# LC_BigOne_-_TLC5940_driver.net
KiCad netlist of a schematic drawn in Altium Designer
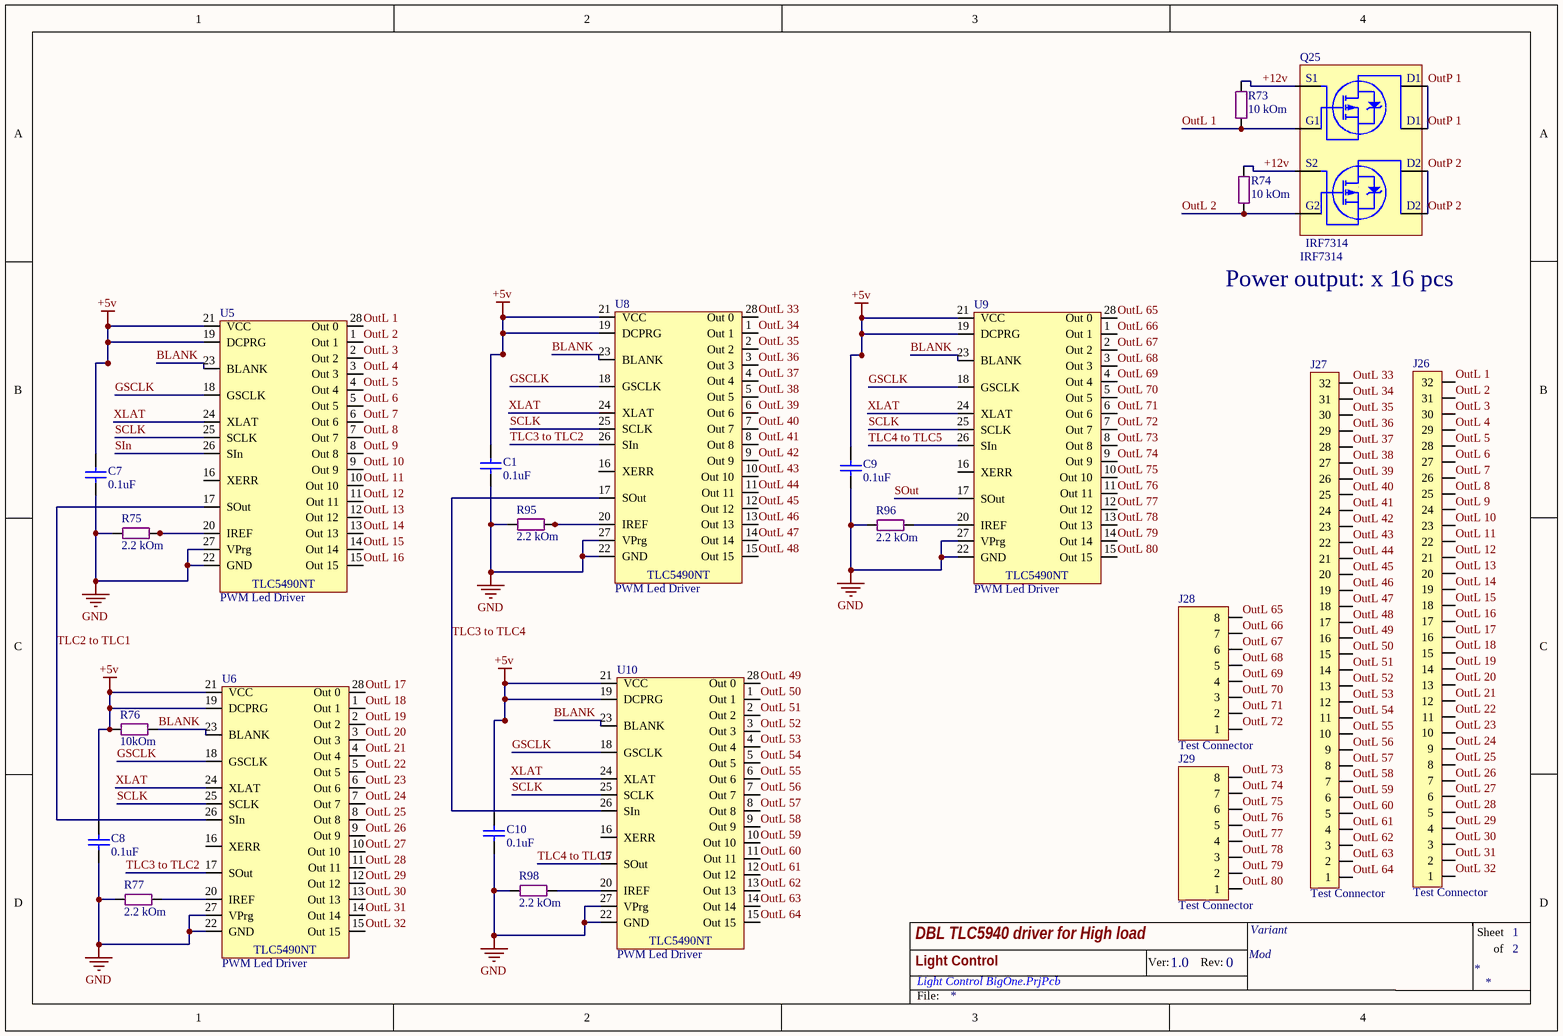
[diagram p0: LC BigOne - TLC5940 driver.SchDoc]

(export (version "E")
  (design (tool "Eeschema 10.0.6"))
  (components
    (comp (ref "C1")
      (value "0.1uF")
      (footprint "Capacitor:SMD 0805 (2012)")
      (description "Capacitor")
      (libsource (lib "Capacitor") (part "Cap SMD 0402-1812"))
    )
    (comp (ref "C7")
      (value "0.1uF")
      (footprint "Capacitor:SMD 0805 (2012)")
      (description "Capacitor")
      (libsource (lib "Capacitor") (part "Cap SMD 0402-1812"))
    )
    (comp (ref "C8")
      (value "0.1uF")
      (footprint "Capacitor:SMD 0805 (2012)")
      (description "Capacitor")
      (libsource (lib "Capacitor") (part "Cap SMD 0402-1812"))
    )
    (comp (ref "C9")
      (value "0.1uF")
      (footprint "Capacitor:SMD 0805 (2012)")
      (description "Capacitor")
      (libsource (lib "Capacitor") (part "Cap SMD 0402-1812"))
    )
    (comp (ref "C10")
      (value "0.1uF")
      (footprint "Capacitor:SMD 0805 (2012)")
      (description "Capacitor")
      (libsource (lib "Capacitor") (part "Cap SMD 0402-1812"))
    )
    (comp (ref "J26")
      (value "Test Connector")
      (footprint "Connector:LINE 2.54 x 32")
      (description "Vert, Sgl line, Male")
      (libsource (lib "Connector") (part "PLS-32"))
    )
    (comp (ref "J27")
      (value "Test Connector")
      (footprint "Connector:LINE 2.54 x 32")
      (description "Vert, Sgl line, Male")
      (libsource (lib "Connector") (part "PLS-32"))
    )
    (comp (ref "J28")
      (value "Test Connector")
      (footprint "Connector:Line 2.54 x 8")
      (description "Vert, Sgl line, Male")
      (libsource (lib "Connector") (part "PLS-8"))
    )
    (comp (ref "J29")
      (value "Test Connector")
      (footprint "Connector:Line 2.54 x 8")
      (description "Vert, Sgl line, Male")
      (libsource (lib "Connector") (part "PLS-8"))
    )
    (comp (ref "Q25")
      (value "IRF7314")
      (footprint "GeneralCases:SO8")
      (description "Dual P-Ch  20V - 0.058Ω - 5.3A")
      (libsource (lib "Transistor") (part "IRF7314"))
    )
    (comp (ref "R73")
      (value "10 kOm")
      (footprint "PassiveComponents:SMD 0805 (2012)")
      (libsource (lib "PassiveComponents") (part "Res All Types"))
    )
    (comp (ref "R74")
      (value "10 kOm")
      (footprint "PassiveComponents:SMD 0805 (2012)")
      (libsource (lib "PassiveComponents") (part "Res All Types"))
    )
    (comp (ref "R75")
      (value "2.2 kOm")
      (footprint "PassiveComponents:SMD 0805 (2012)")
      (libsource (lib "PassiveComponents") (part "Res All Types"))
    )
    (comp (ref "R76")
      (value "10kOm")
      (footprint "PassiveComponents:SMD 0805 (2012)")
      (libsource (lib "PassiveComponents") (part "Res All Types"))
    )
    (comp (ref "R77")
      (value "2.2 kOm")
      (footprint "PassiveComponents:SMD 0805 (2012)")
      (libsource (lib "PassiveComponents") (part "Res All Types"))
    )
    (comp (ref "R95")
      (value "2.2 kOm")
      (footprint "PassiveComponents:SMD 0805 (2012)")
      (libsource (lib "PassiveComponents") (part "Res All Types"))
    )
    (comp (ref "R96")
      (value "2.2 kOm")
      (footprint "PassiveComponents:SMD 0805 (2012)")
      (libsource (lib "PassiveComponents") (part "Res All Types"))
    )
    (comp (ref "R98")
      (value "2.2 kOm")
      (footprint "PassiveComponents:SMD 0805 (2012)")
      (libsource (lib "PassiveComponents") (part "Res All Types"))
    )
    (comp (ref "U5")
      (value "PWM Led Driver")
      (footprint "GeneralCases:DIP-28 (OVAL)")
      (description "16-Channel LED Driver With DOT Correction and Grayscale PWM Control")
      (libsource (lib "Chips") (part "TLC5940"))
    )
    (comp (ref "U6")
      (value "PWM Led Driver")
      (footprint "GeneralCases:DIP-28 (OVAL)")
      (description "16-Channel LED Driver With DOT Correction and Grayscale PWM Control")
      (libsource (lib "Chips") (part "TLC5940"))
    )
    (comp (ref "U8")
      (value "PWM Led Driver")
      (footprint "GeneralCases:DIP-28 (OVAL)")
      (description "16-Channel LED Driver With DOT Correction and Grayscale PWM Control")
      (libsource (lib "Chips") (part "TLC5940"))
    )
    (comp (ref "U9")
      (value "PWM Led Driver")
      (footprint "GeneralCases:DIP-28 (OVAL)")
      (description "16-Channel LED Driver With DOT Correction and Grayscale PWM Control")
      (libsource (lib "Chips") (part "TLC5940"))
    )
    (comp (ref "U10")
      (value "PWM Led Driver")
      (footprint "GeneralCases:DIP-28 (OVAL)")
      (description "16-Channel LED Driver With DOT Correction and Grayscale PWM Control")
      (libsource (lib "Chips") (part "TLC5940"))
    )
  )
  (nets
    (net (code "1") (name "+5v") (class "Default")
      (node (ref "C1") (pin "1") (pinfunction "1_1") (pintype "passive"))
      (node (ref "C10") (pin "1") (pinfunction "1_1") (pintype "passive"))
      (node (ref "C7") (pin "1") (pinfunction "1_1") (pintype "passive"))
      (node (ref "C8") (pin "1") (pinfunction "1_1") (pintype "passive"))
      (node (ref "C9") (pin "1") (pinfunction "1_1") (pintype "passive"))
      (node (ref "R76") (pin "1") (pinfunction "1_1") (pintype "passive"))
      (node (ref "U10") (pin "19") (pinfunction "DCPRG_19") (pintype "passive"))
      (node (ref "U10") (pin "21") (pinfunction "VCC_21") (pintype "passive"))
      (node (ref "U5") (pin "19") (pinfunction "DCPRG_19") (pintype "passive"))
      (node (ref "U5") (pin "21") (pinfunction "VCC_21") (pintype "passive"))
      (node (ref "U6") (pin "19") (pinfunction "DCPRG_19") (pintype "passive"))
      (node (ref "U6") (pin "21") (pinfunction "VCC_21") (pintype "passive"))
      (node (ref "U8") (pin "19") (pinfunction "DCPRG_19") (pintype "passive"))
      (node (ref "U8") (pin "21") (pinfunction "VCC_21") (pintype "passive"))
      (node (ref "U9") (pin "19") (pinfunction "DCPRG_19") (pintype "passive"))
      (node (ref "U9") (pin "21") (pinfunction "VCC_21") (pintype "passive"))
    )
    (net (code "2") (name "/+12v") (class "Default")
      (node (ref "Q25") (pin "1") (pinfunction "S_1") (pintype "passive"))
      (node (ref "Q25") (pin "3") (pinfunction "S_3") (pintype "passive"))
      (node (ref "R73") (pin "2") (pinfunction "2_2") (pintype "passive"))
      (node (ref "R74") (pin "2") (pinfunction "2_2") (pintype "passive"))
    )
    (net (code "3") (name "/BLANK") (class "Default")
      (node (ref "R76") (pin "2") (pinfunction "2_2") (pintype "passive"))
      (node (ref "U10") (pin "23") (pinfunction "BLANK_23") (pintype "passive"))
      (node (ref "U5") (pin "23") (pinfunction "BLANK_23") (pintype "passive"))
      (node (ref "U6") (pin "23") (pinfunction "BLANK_23") (pintype "passive"))
      (node (ref "U8") (pin "23") (pinfunction "BLANK_23") (pintype "passive"))
      (node (ref "U9") (pin "23") (pinfunction "BLANK_23") (pintype "passive"))
    )
    (net (code "4") (name "/GSCLK") (class "Default")
      (node (ref "U10") (pin "18") (pinfunction "GSCLK_18") (pintype "passive"))
      (node (ref "U5") (pin "18") (pinfunction "GSCLK_18") (pintype "passive"))
      (node (ref "U6") (pin "18") (pinfunction "GSCLK_18") (pintype "passive"))
      (node (ref "U8") (pin "18") (pinfunction "GSCLK_18") (pintype "passive"))
      (node (ref "U9") (pin "18") (pinfunction "GSCLK_18") (pintype "passive"))
    )
    (net (code "5") (name "/OutL 1") (class "Default")
      (node (ref "J26") (pin "32") (pinfunction "32_32") (pintype "passive"))
      (node (ref "Q25") (pin "2") (pinfunction "G_2") (pintype "passive"))
      (node (ref "R73") (pin "1") (pinfunction "1_1") (pintype "passive"))
      (node (ref "U5") (pin "28") (pinfunction "Out_0_28") (pintype "passive"))
    )
    (net (code "6") (name "/OutL 2") (class "Default")
      (node (ref "J26") (pin "31") (pinfunction "31_31") (pintype "passive"))
      (node (ref "Q25") (pin "4") (pinfunction "G_4") (pintype "passive"))
      (node (ref "R74") (pin "1") (pinfunction "1_1") (pintype "passive"))
      (node (ref "U5") (pin "1") (pinfunction "Out_1_1") (pintype "passive"))
    )
    (net (code "7") (name "/OutL 3") (class "Default")
      (node (ref "J26") (pin "30") (pinfunction "30_30") (pintype "passive"))
      (node (ref "U5") (pin "2") (pinfunction "Out_2_2") (pintype "passive"))
    )
    (net (code "8") (name "/OutL 4") (class "Default")
      (node (ref "J26") (pin "29") (pinfunction "29_29") (pintype "passive"))
      (node (ref "U5") (pin "3") (pinfunction "Out_3_3") (pintype "passive"))
    )
    (net (code "9") (name "/OutL 5") (class "Default")
      (node (ref "J26") (pin "28") (pinfunction "28_28") (pintype "passive"))
      (node (ref "U5") (pin "4") (pinfunction "Out_4_4") (pintype "passive"))
    )
    (net (code "10") (name "/OutL 6") (class "Default")
      (node (ref "J26") (pin "27") (pinfunction "27_27") (pintype "passive"))
      (node (ref "U5") (pin "5") (pinfunction "Out_5_5") (pintype "passive"))
    )
    (net (code "11") (name "/OutL 7") (class "Default")
      (node (ref "J26") (pin "26") (pinfunction "26_26") (pintype "passive"))
      (node (ref "U5") (pin "6") (pinfunction "Out_6_6") (pintype "passive"))
    )
    (net (code "12") (name "/OutL 8") (class "Default")
      (node (ref "J26") (pin "25") (pinfunction "25_25") (pintype "passive"))
      (node (ref "U5") (pin "7") (pinfunction "Out_7_7") (pintype "passive"))
    )
    (net (code "13") (name "/OutL 9") (class "Default")
      (node (ref "J26") (pin "24") (pinfunction "24_24") (pintype "passive"))
      (node (ref "U5") (pin "8") (pinfunction "Out_8_8") (pintype "passive"))
    )
    (net (code "14") (name "/OutL 10") (class "Default")
      (node (ref "J26") (pin "23") (pinfunction "23_23") (pintype "passive"))
      (node (ref "U5") (pin "9") (pinfunction "Out_9_9") (pintype "passive"))
    )
    (net (code "15") (name "/OutL 11") (class "Default")
      (node (ref "J26") (pin "22") (pinfunction "22_22") (pintype "passive"))
      (node (ref "U5") (pin "10") (pinfunction "Out_10_10") (pintype "passive"))
    )
    (net (code "16") (name "/OutL 12") (class "Default")
      (node (ref "J26") (pin "21") (pinfunction "21_21") (pintype "passive"))
      (node (ref "U5") (pin "11") (pinfunction "Out_11_11") (pintype "passive"))
    )
    (net (code "17") (name "/OutL 13") (class "Default")
      (node (ref "J26") (pin "20") (pinfunction "20_20") (pintype "passive"))
      (node (ref "U5") (pin "12") (pinfunction "Out_12_12") (pintype "passive"))
    )
    (net (code "18") (name "/OutL 14") (class "Default")
      (node (ref "J26") (pin "19") (pinfunction "19_19") (pintype "passive"))
      (node (ref "U5") (pin "13") (pinfunction "Out_13_13") (pintype "passive"))
    )
    (net (code "19") (name "/OutL 15") (class "Default")
      (node (ref "J26") (pin "18") (pinfunction "18_18") (pintype "passive"))
      (node (ref "U5") (pin "14") (pinfunction "Out_14_14") (pintype "passive"))
    )
    (net (code "20") (name "/OutL 16") (class "Default")
      (node (ref "J26") (pin "17") (pinfunction "17_17") (pintype "passive"))
      (node (ref "U5") (pin "15") (pinfunction "Out_15_15") (pintype "passive"))
    )
    (net (code "21") (name "/OutL 17") (class "Default")
      (node (ref "J26") (pin "16") (pinfunction "16_16") (pintype "passive"))
      (node (ref "U6") (pin "28") (pinfunction "Out_0_28") (pintype "passive"))
    )
    (net (code "22") (name "/OutL 18") (class "Default")
      (node (ref "J26") (pin "15") (pinfunction "15_15") (pintype "passive"))
      (node (ref "U6") (pin "1") (pinfunction "Out_1_1") (pintype "passive"))
    )
    (net (code "23") (name "/OutL 19") (class "Default")
      (node (ref "J26") (pin "14") (pinfunction "14_14") (pintype "passive"))
      (node (ref "U6") (pin "2") (pinfunction "Out_2_2") (pintype "passive"))
    )
    (net (code "24") (name "/OutL 20") (class "Default")
      (node (ref "J26") (pin "13") (pinfunction "13_13") (pintype "passive"))
      (node (ref "U6") (pin "3") (pinfunction "Out_3_3") (pintype "passive"))
    )
    (net (code "25") (name "/OutL 21") (class "Default")
      (node (ref "J26") (pin "12") (pinfunction "12_12") (pintype "passive"))
      (node (ref "U6") (pin "4") (pinfunction "Out_4_4") (pintype "passive"))
    )
    (net (code "26") (name "/OutL 22") (class "Default")
      (node (ref "J26") (pin "11") (pinfunction "11_11") (pintype "passive"))
      (node (ref "U6") (pin "5") (pinfunction "Out_5_5") (pintype "passive"))
    )
    (net (code "27") (name "/OutL 23") (class "Default")
      (node (ref "J26") (pin "10") (pinfunction "10_10") (pintype "passive"))
      (node (ref "U6") (pin "6") (pinfunction "Out_6_6") (pintype "passive"))
    )
    (net (code "28") (name "/OutL 24") (class "Default")
      (node (ref "J26") (pin "9") (pinfunction "9_9") (pintype "passive"))
      (node (ref "U6") (pin "7") (pinfunction "Out_7_7") (pintype "passive"))
    )
    (net (code "29") (name "/OutL 25") (class "Default")
      (node (ref "J26") (pin "8") (pinfunction "8_8") (pintype "passive"))
      (node (ref "U6") (pin "8") (pinfunction "Out_8_8") (pintype "passive"))
    )
    (net (code "30") (name "/OutL 26") (class "Default")
      (node (ref "J26") (pin "7") (pinfunction "7_7") (pintype "passive"))
      (node (ref "U6") (pin "9") (pinfunction "Out_9_9") (pintype "passive"))
    )
    (net (code "31") (name "/OutL 27") (class "Default")
      (node (ref "J26") (pin "6") (pinfunction "6_6") (pintype "passive"))
      (node (ref "U6") (pin "10") (pinfunction "Out_10_10") (pintype "passive"))
    )
    (net (code "32") (name "/OutL 28") (class "Default")
      (node (ref "J26") (pin "5") (pinfunction "5_5") (pintype "passive"))
      (node (ref "U6") (pin "11") (pinfunction "Out_11_11") (pintype "passive"))
    )
    (net (code "33") (name "/OutL 29") (class "Default")
      (node (ref "J26") (pin "4") (pinfunction "4_4") (pintype "passive"))
      (node (ref "U6") (pin "12") (pinfunction "Out_12_12") (pintype "passive"))
    )
    (net (code "34") (name "/OutL 30") (class "Default")
      (node (ref "J26") (pin "3") (pinfunction "3_3") (pintype "passive"))
      (node (ref "U6") (pin "13") (pinfunction "Out_13_13") (pintype "passive"))
    )
    (net (code "35") (name "/OutL 31") (class "Default")
      (node (ref "J26") (pin "2") (pinfunction "2_2") (pintype "passive"))
      (node (ref "U6") (pin "14") (pinfunction "Out_14_14") (pintype "passive"))
    )
    (net (code "36") (name "/OutL 32") (class "Default")
      (node (ref "J26") (pin "1") (pinfunction "1_1") (pintype "passive"))
      (node (ref "U6") (pin "15") (pinfunction "Out_15_15") (pintype "passive"))
    )
    (net (code "37") (name "/OutL 33") (class "Default")
      (node (ref "J27") (pin "32") (pinfunction "32_32") (pintype "passive"))
      (node (ref "U8") (pin "28") (pinfunction "Out_0_28") (pintype "passive"))
    )
    (net (code "38") (name "/OutL 34") (class "Default")
      (node (ref "J27") (pin "31") (pinfunction "31_31") (pintype "passive"))
      (node (ref "U8") (pin "1") (pinfunction "Out_1_1") (pintype "passive"))
    )
    (net (code "39") (name "/OutL 35") (class "Default")
      (node (ref "J27") (pin "30") (pinfunction "30_30") (pintype "passive"))
      (node (ref "U8") (pin "2") (pinfunction "Out_2_2") (pintype "passive"))
    )
    (net (code "40") (name "/OutL 36") (class "Default")
      (node (ref "J27") (pin "29") (pinfunction "29_29") (pintype "passive"))
      (node (ref "U8") (pin "3") (pinfunction "Out_3_3") (pintype "passive"))
    )
    (net (code "41") (name "/OutL 37") (class "Default")
      (node (ref "J27") (pin "28") (pinfunction "28_28") (pintype "passive"))
      (node (ref "U8") (pin "4") (pinfunction "Out_4_4") (pintype "passive"))
    )
    (net (code "42") (name "/OutL 38") (class "Default")
      (node (ref "J27") (pin "27") (pinfunction "27_27") (pintype "passive"))
      (node (ref "U8") (pin "5") (pinfunction "Out_5_5") (pintype "passive"))
    )
    (net (code "43") (name "/OutL 39") (class "Default")
      (node (ref "J27") (pin "26") (pinfunction "26_26") (pintype "passive"))
      (node (ref "U8") (pin "6") (pinfunction "Out_6_6") (pintype "passive"))
    )
    (net (code "44") (name "/OutL 40") (class "Default")
      (node (ref "J27") (pin "25") (pinfunction "25_25") (pintype "passive"))
      (node (ref "U8") (pin "7") (pinfunction "Out_7_7") (pintype "passive"))
    )
    (net (code "45") (name "/OutL 41") (class "Default")
      (node (ref "J27") (pin "24") (pinfunction "24_24") (pintype "passive"))
      (node (ref "U8") (pin "8") (pinfunction "Out_8_8") (pintype "passive"))
    )
    (net (code "46") (name "/OutL 42") (class "Default")
      (node (ref "J27") (pin "23") (pinfunction "23_23") (pintype "passive"))
      (node (ref "U8") (pin "9") (pinfunction "Out_9_9") (pintype "passive"))
    )
    (net (code "47") (name "/OutL 43") (class "Default")
      (node (ref "J27") (pin "22") (pinfunction "22_22") (pintype "passive"))
      (node (ref "U8") (pin "10") (pinfunction "Out_10_10") (pintype "passive"))
    )
    (net (code "48") (name "/OutL 44") (class "Default")
      (node (ref "J27") (pin "21") (pinfunction "21_21") (pintype "passive"))
      (node (ref "U8") (pin "11") (pinfunction "Out_11_11") (pintype "passive"))
    )
    (net (code "49") (name "/OutL 45") (class "Default")
      (node (ref "J27") (pin "20") (pinfunction "20_20") (pintype "passive"))
      (node (ref "U8") (pin "12") (pinfunction "Out_12_12") (pintype "passive"))
    )
    (net (code "50") (name "/OutL 46") (class "Default")
      (node (ref "J27") (pin "19") (pinfunction "19_19") (pintype "passive"))
      (node (ref "U8") (pin "13") (pinfunction "Out_13_13") (pintype "passive"))
    )
    (net (code "51") (name "/OutL 47") (class "Default")
      (node (ref "J27") (pin "18") (pinfunction "18_18") (pintype "passive"))
      (node (ref "U8") (pin "14") (pinfunction "Out_14_14") (pintype "passive"))
    )
    (net (code "52") (name "/OutL 48") (class "Default")
      (node (ref "J27") (pin "17") (pinfunction "17_17") (pintype "passive"))
      (node (ref "U8") (pin "15") (pinfunction "Out_15_15") (pintype "passive"))
    )
    (net (code "53") (name "/OutL 49") (class "Default")
      (node (ref "J27") (pin "16") (pinfunction "16_16") (pintype "passive"))
      (node (ref "U10") (pin "28") (pinfunction "Out_0_28") (pintype "passive"))
    )
    (net (code "54") (name "/OutL 50") (class "Default")
      (node (ref "J27") (pin "15") (pinfunction "15_15") (pintype "passive"))
      (node (ref "U10") (pin "1") (pinfunction "Out_1_1") (pintype "passive"))
    )
    (net (code "55") (name "/OutL 51") (class "Default")
      (node (ref "J27") (pin "14") (pinfunction "14_14") (pintype "passive"))
      (node (ref "U10") (pin "2") (pinfunction "Out_2_2") (pintype "passive"))
    )
    (net (code "56") (name "/OutL 52") (class "Default")
      (node (ref "J27") (pin "13") (pinfunction "13_13") (pintype "passive"))
      (node (ref "U10") (pin "3") (pinfunction "Out_3_3") (pintype "passive"))
    )
    (net (code "57") (name "/OutL 53") (class "Default")
      (node (ref "J27") (pin "12") (pinfunction "12_12") (pintype "passive"))
      (node (ref "U10") (pin "4") (pinfunction "Out_4_4") (pintype "passive"))
    )
    (net (code "58") (name "/OutL 54") (class "Default")
      (node (ref "J27") (pin "11") (pinfunction "11_11") (pintype "passive"))
      (node (ref "U10") (pin "5") (pinfunction "Out_5_5") (pintype "passive"))
    )
    (net (code "59") (name "/OutL 55") (class "Default")
      (node (ref "J27") (pin "10") (pinfunction "10_10") (pintype "passive"))
      (node (ref "U10") (pin "6") (pinfunction "Out_6_6") (pintype "passive"))
    )
    (net (code "60") (name "/OutL 56") (class "Default")
      (node (ref "J27") (pin "9") (pinfunction "9_9") (pintype "passive"))
      (node (ref "U10") (pin "7") (pinfunction "Out_7_7") (pintype "passive"))
    )
    (net (code "61") (name "/OutL 57") (class "Default")
      (node (ref "J27") (pin "8") (pinfunction "8_8") (pintype "passive"))
      (node (ref "U10") (pin "8") (pinfunction "Out_8_8") (pintype "passive"))
    )
    (net (code "62") (name "/OutL 58") (class "Default")
      (node (ref "J27") (pin "7") (pinfunction "7_7") (pintype "passive"))
      (node (ref "U10") (pin "9") (pinfunction "Out_9_9") (pintype "passive"))
    )
    (net (code "63") (name "/OutL 59") (class "Default")
      (node (ref "J27") (pin "6") (pinfunction "6_6") (pintype "passive"))
      (node (ref "U10") (pin "10") (pinfunction "Out_10_10") (pintype "passive"))
    )
    (net (code "64") (name "/OutL 60") (class "Default")
      (node (ref "J27") (pin "5") (pinfunction "5_5") (pintype "passive"))
      (node (ref "U10") (pin "11") (pinfunction "Out_11_11") (pintype "passive"))
    )
    (net (code "65") (name "/OutL 61") (class "Default")
      (node (ref "J27") (pin "4") (pinfunction "4_4") (pintype "passive"))
      (node (ref "U10") (pin "12") (pinfunction "Out_12_12") (pintype "passive"))
    )
    (net (code "66") (name "/OutL 62") (class "Default")
      (node (ref "J27") (pin "3") (pinfunction "3_3") (pintype "passive"))
      (node (ref "U10") (pin "13") (pinfunction "Out_13_13") (pintype "passive"))
    )
    (net (code "67") (name "/OutL 63") (class "Default")
      (node (ref "J27") (pin "2") (pinfunction "2_2") (pintype "passive"))
      (node (ref "U10") (pin "14") (pinfunction "Out_14_14") (pintype "passive"))
    )
    (net (code "68") (name "/OutL 64") (class "Default")
      (node (ref "J27") (pin "1") (pinfunction "1_1") (pintype "passive"))
      (node (ref "U10") (pin "15") (pinfunction "Out_15_15") (pintype "passive"))
    )
    (net (code "69") (name "/OutL 65") (class "Default")
      (node (ref "J28") (pin "8") (pinfunction "8_8") (pintype "passive"))
      (node (ref "U9") (pin "28") (pinfunction "Out_0_28") (pintype "passive"))
    )
    (net (code "70") (name "/OutL 66") (class "Default")
      (node (ref "J28") (pin "7") (pinfunction "7_7") (pintype "passive"))
      (node (ref "U9") (pin "1") (pinfunction "Out_1_1") (pintype "passive"))
    )
    (net (code "71") (name "/OutL 67") (class "Default")
      (node (ref "J28") (pin "6") (pinfunction "6_6") (pintype "passive"))
      (node (ref "U9") (pin "2") (pinfunction "Out_2_2") (pintype "passive"))
    )
    (net (code "72") (name "/OutL 68") (class "Default")
      (node (ref "J28") (pin "5") (pinfunction "5_5") (pintype "passive"))
      (node (ref "U9") (pin "3") (pinfunction "Out_3_3") (pintype "passive"))
    )
    (net (code "73") (name "/OutL 69") (class "Default")
      (node (ref "J28") (pin "4") (pinfunction "4_4") (pintype "passive"))
      (node (ref "U9") (pin "4") (pinfunction "Out_4_4") (pintype "passive"))
    )
    (net (code "74") (name "/OutL 70") (class "Default")
      (node (ref "J28") (pin "3") (pinfunction "3_3") (pintype "passive"))
      (node (ref "U9") (pin "5") (pinfunction "Out_5_5") (pintype "passive"))
    )
    (net (code "75") (name "/OutL 71") (class "Default")
      (node (ref "J28") (pin "2") (pinfunction "2_2") (pintype "passive"))
      (node (ref "U9") (pin "6") (pinfunction "Out_6_6") (pintype "passive"))
    )
    (net (code "76") (name "/OutL 72") (class "Default")
      (node (ref "J28") (pin "1") (pinfunction "1_1") (pintype "passive"))
      (node (ref "U9") (pin "7") (pinfunction "Out_7_7") (pintype "passive"))
    )
    (net (code "77") (name "/OutL 73") (class "Default")
      (node (ref "J29") (pin "8") (pinfunction "8_8") (pintype "passive"))
      (node (ref "U9") (pin "8") (pinfunction "Out_8_8") (pintype "passive"))
    )
    (net (code "78") (name "/OutL 74") (class "Default")
      (node (ref "J29") (pin "7") (pinfunction "7_7") (pintype "passive"))
      (node (ref "U9") (pin "9") (pinfunction "Out_9_9") (pintype "passive"))
    )
    (net (code "79") (name "/OutL 75") (class "Default")
      (node (ref "J29") (pin "6") (pinfunction "6_6") (pintype "passive"))
      (node (ref "U9") (pin "10") (pinfunction "Out_10_10") (pintype "passive"))
    )
    (net (code "80") (name "/OutL 76") (class "Default")
      (node (ref "J29") (pin "5") (pinfunction "5_5") (pintype "passive"))
      (node (ref "U9") (pin "11") (pinfunction "Out_11_11") (pintype "passive"))
    )
    (net (code "81") (name "/OutL 77") (class "Default")
      (node (ref "J29") (pin "4") (pinfunction "4_4") (pintype "passive"))
      (node (ref "U9") (pin "12") (pinfunction "Out_12_12") (pintype "passive"))
    )
    (net (code "82") (name "/OutL 78") (class "Default")
      (node (ref "J29") (pin "3") (pinfunction "3_3") (pintype "passive"))
      (node (ref "U9") (pin "13") (pinfunction "Out_13_13") (pintype "passive"))
    )
    (net (code "83") (name "/OutL 79") (class "Default")
      (node (ref "J29") (pin "2") (pinfunction "2_2") (pintype "passive"))
      (node (ref "U9") (pin "14") (pinfunction "Out_14_14") (pintype "passive"))
    )
    (net (code "84") (name "/OutL 80") (class "Default")
      (node (ref "J29") (pin "1") (pinfunction "1_1") (pintype "passive"))
      (node (ref "U9") (pin "15") (pinfunction "Out_15_15") (pintype "passive"))
    )
    (net (code "85") (name "/OutP 1") (class "Default")
      (node (ref "Q25") (pin "7") (pinfunction "D_7") (pintype "passive"))
      (node (ref "Q25") (pin "8") (pinfunction "D_8") (pintype "passive"))
    )
    (net (code "86") (name "/OutP 2") (class "Default")
      (node (ref "Q25") (pin "5") (pinfunction "D_5") (pintype "passive"))
      (node (ref "Q25") (pin "6") (pinfunction "D_6") (pintype "passive"))
    )
    (net (code "87") (name "/SCLK") (class "Default")
      (node (ref "U10") (pin "25") (pinfunction "SCLK_25") (pintype "passive"))
      (node (ref "U5") (pin "25") (pinfunction "SCLK_25") (pintype "passive"))
      (node (ref "U6") (pin "25") (pinfunction "SCLK_25") (pintype "passive"))
      (node (ref "U8") (pin "25") (pinfunction "SCLK_25") (pintype "passive"))
      (node (ref "U9") (pin "25") (pinfunction "SCLK_25") (pintype "passive"))
    )
    (net (code "88") (name "/SIn") (class "Default")
      (node (ref "U5") (pin "26") (pinfunction "SIn_26") (pintype "passive"))
    )
    (net (code "89") (name "/SOut") (class "Default")
      (node (ref "U9") (pin "17") (pinfunction "SOut_17") (pintype "passive"))
    )
    (net (code "90") (name "/TLC2 to TLC1") (class "Default")
      (node (ref "U5") (pin "17") (pinfunction "SOut_17") (pintype "passive"))
      (node (ref "U6") (pin "26") (pinfunction "SIn_26") (pintype "passive"))
    )
    (net (code "91") (name "/TLC3 to TLC2") (class "Default")
      (node (ref "U6") (pin "17") (pinfunction "SOut_17") (pintype "passive"))
      (node (ref "U8") (pin "26") (pinfunction "SIn_26") (pintype "passive"))
    )
    (net (code "92") (name "/TLC3 to TLC4") (class "Default")
      (node (ref "U10") (pin "26") (pinfunction "SIn_26") (pintype "passive"))
      (node (ref "U8") (pin "17") (pinfunction "SOut_17") (pintype "passive"))
    )
    (net (code "93") (name "/TLC4 to TLC5") (class "Default")
      (node (ref "U10") (pin "17") (pinfunction "SOut_17") (pintype "passive"))
      (node (ref "U9") (pin "26") (pinfunction "SIn_26") (pintype "passive"))
    )
    (net (code "94") (name "/XLAT") (class "Default")
      (node (ref "U10") (pin "24") (pinfunction "XLAT_24") (pintype "passive"))
      (node (ref "U5") (pin "24") (pinfunction "XLAT_24") (pintype "passive"))
      (node (ref "U6") (pin "24") (pinfunction "XLAT_24") (pintype "passive"))
      (node (ref "U8") (pin "24") (pinfunction "XLAT_24") (pintype "passive"))
      (node (ref "U9") (pin "24") (pinfunction "XLAT_24") (pintype "passive"))
    )
    (net (code "95") (name "GND") (class "Default")
      (node (ref "C1") (pin "2") (pinfunction "2_2") (pintype "passive"))
      (node (ref "C10") (pin "2") (pinfunction "2_2") (pintype "passive"))
      (node (ref "C7") (pin "2") (pinfunction "2_2") (pintype "passive"))
      (node (ref "C8") (pin "2") (pinfunction "2_2") (pintype "passive"))
      (node (ref "C9") (pin "2") (pinfunction "2_2") (pintype "passive"))
      (node (ref "R75") (pin "2") (pinfunction "2_2") (pintype "passive"))
      (node (ref "R77") (pin "2") (pinfunction "2_2") (pintype "passive"))
      (node (ref "R95") (pin "2") (pinfunction "2_2") (pintype "passive"))
      (node (ref "R96") (pin "2") (pinfunction "2_2") (pintype "passive"))
      (node (ref "R98") (pin "2") (pinfunction "2_2") (pintype "passive"))
      (node (ref "U10") (pin "22") (pinfunction "GND_22") (pintype "passive"))
      (node (ref "U10") (pin "27") (pinfunction "VPrg_27") (pintype "passive"))
      (node (ref "U5") (pin "22") (pinfunction "GND_22") (pintype "passive"))
      (node (ref "U5") (pin "27") (pinfunction "VPrg_27") (pintype "passive"))
      (node (ref "U6") (pin "22") (pinfunction "GND_22") (pintype "passive"))
      (node (ref "U6") (pin "27") (pinfunction "VPrg_27") (pintype "passive"))
      (node (ref "U8") (pin "22") (pinfunction "GND_22") (pintype "passive"))
      (node (ref "U8") (pin "27") (pinfunction "VPrg_27") (pintype "passive"))
      (node (ref "U9") (pin "22") (pinfunction "GND_22") (pintype "passive"))
      (node (ref "U9") (pin "27") (pinfunction "VPrg_27") (pintype "passive"))
    )
    (net (code "96") (name "Net-(U5-IREF)") (class "Default")
      (node (ref "R75") (pin "1") (pinfunction "1_1") (pintype "passive"))
      (node (ref "U5") (pin "20") (pinfunction "IREF_20") (pintype "passive"))
    )
    (net (code "97") (name "Net-(U6-IREF)") (class "Default")
      (node (ref "R77") (pin "1") (pinfunction "1_1") (pintype "passive"))
      (node (ref "U6") (pin "20") (pinfunction "IREF_20") (pintype "passive"))
    )
    (net (code "98") (name "Net-(U8-IREF)") (class "Default")
      (node (ref "R95") (pin "1") (pinfunction "1_1") (pintype "passive"))
      (node (ref "U8") (pin "20") (pinfunction "IREF_20") (pintype "passive"))
    )
    (net (code "99") (name "Net-(U9-IREF)") (class "Default")
      (node (ref "R96") (pin "1") (pinfunction "1_1") (pintype "passive"))
      (node (ref "U9") (pin "20") (pinfunction "IREF_20") (pintype "passive"))
    )
    (net (code "100") (name "Net-(U10-IREF)") (class "Default")
      (node (ref "R98") (pin "1") (pinfunction "1_1") (pintype "passive"))
      (node (ref "U10") (pin "20") (pinfunction "IREF_20") (pintype "passive"))
    )
    (net (code "101") (name "unconnected-(U5-XERR-Pad16)") (class "Default")
      (node (ref "U5") (pin "16") (pinfunction "XERR_16") (pintype "passive"))
    )
    (net (code "102") (name "unconnected-(U6-XERR-Pad16)") (class "Default")
      (node (ref "U6") (pin "16") (pinfunction "XERR_16") (pintype "passive"))
    )
    (net (code "103") (name "unconnected-(U8-XERR-Pad16)") (class "Default")
      (node (ref "U8") (pin "16") (pinfunction "XERR_16") (pintype "passive"))
    )
    (net (code "104") (name "unconnected-(U9-XERR-Pad16)") (class "Default")
      (node (ref "U9") (pin "16") (pinfunction "XERR_16") (pintype "passive"))
    )
    (net (code "105") (name "unconnected-(U10-XERR-Pad16)") (class "Default")
      (node (ref "U10") (pin "16") (pinfunction "XERR_16") (pintype "passive"))
    )
  )
)
